# NESRGB_AV_MultiOut.net
KiCad netlist of a schematic drawn in EAGLE
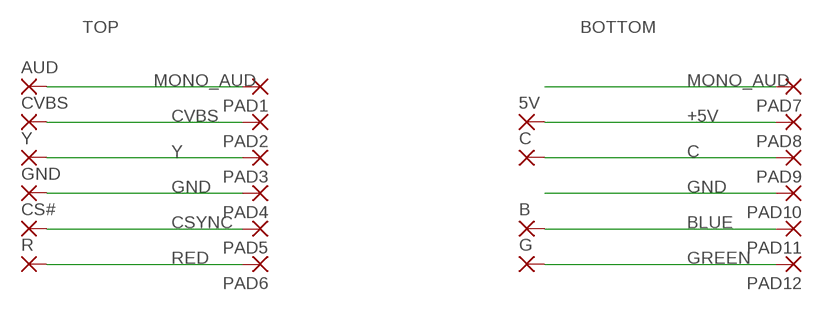
[diagram p0: schematic, sheet 1]

(export (version "E")
  (design (tool "Eeschema 10.0.6"))
  (components
    (comp (ref "5V")
      (value "SMD2")
      (footprint "eagle-import:SMD1,27-2,54")
      (libsource (lib "eagle-import") (part "SMD2"))
    )
    (comp (ref "AUD")
      (value "SMD2")
      (footprint "eagle-import:SMD1,27-2,54")
      (libsource (lib "eagle-import") (part "SMD2"))
    )
    (comp (ref "B")
      (value "SMD2")
      (footprint "eagle-import:SMD1,27-2,54")
      (libsource (lib "eagle-import") (part "SMD2"))
    )
    (comp (ref "C")
      (value "SMD2")
      (footprint "eagle-import:SMD1,27-2,54")
      (libsource (lib "eagle-import") (part "SMD2"))
    )
    (comp (ref "CS#")
      (value "SMD2")
      (footprint "eagle-import:SMD1,27-2,54")
      (libsource (lib "eagle-import") (part "SMD2"))
    )
    (comp (ref "CVBS")
      (value "SMD2")
      (footprint "eagle-import:SMD1,27-2,54")
      (libsource (lib "eagle-import") (part "SMD2"))
    )
    (comp (ref "G")
      (value "SMD2")
      (footprint "eagle-import:SMD1,27-2,54")
      (libsource (lib "eagle-import") (part "SMD2"))
    )
    (comp (ref "GND")
      (value "SMD2")
      (footprint "eagle-import:SMD1,27-2,54")
      (libsource (lib "eagle-import") (part "SMD2"))
    )
    (comp (ref "PAD1")
      (value "SMD_PADNIN_AV")
      (footprint "eagle-import:SMD_NINAV")
      (libsource (lib "eagle-import") (part "SMD_PADNIN_AV"))
    )
    (comp (ref "PAD2")
      (value "SMD_PADNIN_AV")
      (footprint "eagle-import:SMD_NINAV")
      (libsource (lib "eagle-import") (part "SMD_PADNIN_AV"))
    )
    (comp (ref "PAD3")
      (value "SMD_PADNIN_AV")
      (footprint "eagle-import:SMD_NINAV")
      (libsource (lib "eagle-import") (part "SMD_PADNIN_AV"))
    )
    (comp (ref "PAD4")
      (value "SMD_PADNIN_AV")
      (footprint "eagle-import:SMD_NINAV")
      (libsource (lib "eagle-import") (part "SMD_PADNIN_AV"))
    )
    (comp (ref "PAD5")
      (value "SMD_PADNIN_AV")
      (footprint "eagle-import:SMD_NINAV")
      (libsource (lib "eagle-import") (part "SMD_PADNIN_AV"))
    )
    (comp (ref "PAD6")
      (value "SMD_PADNIN_AV")
      (footprint "eagle-import:SMD_NINAV")
      (libsource (lib "eagle-import") (part "SMD_PADNIN_AV"))
    )
    (comp (ref "PAD7")
      (value "SMD_PADNIN_AV")
      (footprint "eagle-import:SMD_NINAV")
      (libsource (lib "eagle-import") (part "SMD_PADNIN_AV"))
    )
    (comp (ref "PAD8")
      (value "SMD_PADNIN_AV")
      (footprint "eagle-import:SMD_NINAV")
      (libsource (lib "eagle-import") (part "SMD_PADNIN_AV"))
    )
    (comp (ref "PAD9")
      (value "SMD_PADNIN_AV")
      (footprint "eagle-import:SMD_NINAV")
      (libsource (lib "eagle-import") (part "SMD_PADNIN_AV"))
    )
    (comp (ref "PAD10")
      (value "SMD_PADNIN_AV")
      (footprint "eagle-import:SMD_NINAV")
      (libsource (lib "eagle-import") (part "SMD_PADNIN_AV"))
    )
    (comp (ref "PAD11")
      (value "SMD_PADNIN_AV")
      (footprint "eagle-import:SMD_NINAV")
      (libsource (lib "eagle-import") (part "SMD_PADNIN_AV"))
    )
    (comp (ref "PAD12")
      (value "SMD_PADNIN_AV")
      (footprint "eagle-import:SMD_NINAV")
      (libsource (lib "eagle-import") (part "SMD_PADNIN_AV"))
    )
    (comp (ref "R")
      (value "SMD2")
      (footprint "eagle-import:SMD1,27-2,54")
      (libsource (lib "eagle-import") (part "SMD2"))
    )
    (comp (ref "Y")
      (value "SMD2")
      (footprint "eagle-import:SMD1,27-2,54")
      (libsource (lib "eagle-import") (part "SMD2"))
    )
  )
  (nets
    (net (code "1") (name "/+5V") (class "Default")
      (node (ref "5V") (pin "1") (pinfunction "P_1") (pintype "passive"))
      (node (ref "PAD8") (pin "1") (pinfunction "P_1") (pintype "passive"))
    )
    (net (code "2") (name "/BLUE") (class "Default")
      (node (ref "B") (pin "1") (pinfunction "P_1") (pintype "passive"))
      (node (ref "PAD11") (pin "1") (pinfunction "P_1") (pintype "passive"))
    )
    (net (code "3") (name "/C") (class "Default")
      (node (ref "C") (pin "1") (pinfunction "P_1") (pintype "passive"))
      (node (ref "PAD9") (pin "1") (pinfunction "P_1") (pintype "passive"))
    )
    (net (code "4") (name "/CSYNC") (class "Default")
      (node (ref "CS#") (pin "1") (pinfunction "P_1") (pintype "passive"))
      (node (ref "PAD5") (pin "1") (pinfunction "P_1") (pintype "passive"))
    )
    (net (code "5") (name "/CVBS") (class "Default")
      (node (ref "CVBS") (pin "1") (pinfunction "P_1") (pintype "passive"))
      (node (ref "PAD2") (pin "1") (pinfunction "P_1") (pintype "passive"))
    )
    (net (code "6") (name "/GND") (class "Default")
      (node (ref "GND") (pin "1") (pinfunction "P_1") (pintype "passive"))
      (node (ref "PAD10") (pin "1") (pinfunction "P_1") (pintype "passive"))
      (node (ref "PAD4") (pin "1") (pinfunction "P_1") (pintype "passive"))
    )
    (net (code "7") (name "/GREEN") (class "Default")
      (node (ref "G") (pin "1") (pinfunction "P_1") (pintype "passive"))
      (node (ref "PAD12") (pin "1") (pinfunction "P_1") (pintype "passive"))
    )
    (net (code "8") (name "/MONO_AUD") (class "Default")
      (node (ref "AUD") (pin "1") (pinfunction "P_1") (pintype "passive"))
      (node (ref "PAD1") (pin "1") (pinfunction "P_1") (pintype "passive"))
      (node (ref "PAD7") (pin "1") (pinfunction "P_1") (pintype "passive"))
    )
    (net (code "9") (name "/RED") (class "Default")
      (node (ref "PAD6") (pin "1") (pinfunction "P_1") (pintype "passive"))
      (node (ref "R") (pin "1") (pinfunction "P_1") (pintype "passive"))
    )
    (net (code "10") (name "/Y") (class "Default")
      (node (ref "PAD3") (pin "1") (pinfunction "P_1") (pintype "passive"))
      (node (ref "Y") (pin "1") (pinfunction "P_1") (pintype "passive"))
    )
  )
)
